# P10_ETH0_RGMII.net
KiCad netlist of a schematic drawn in Altium Designer
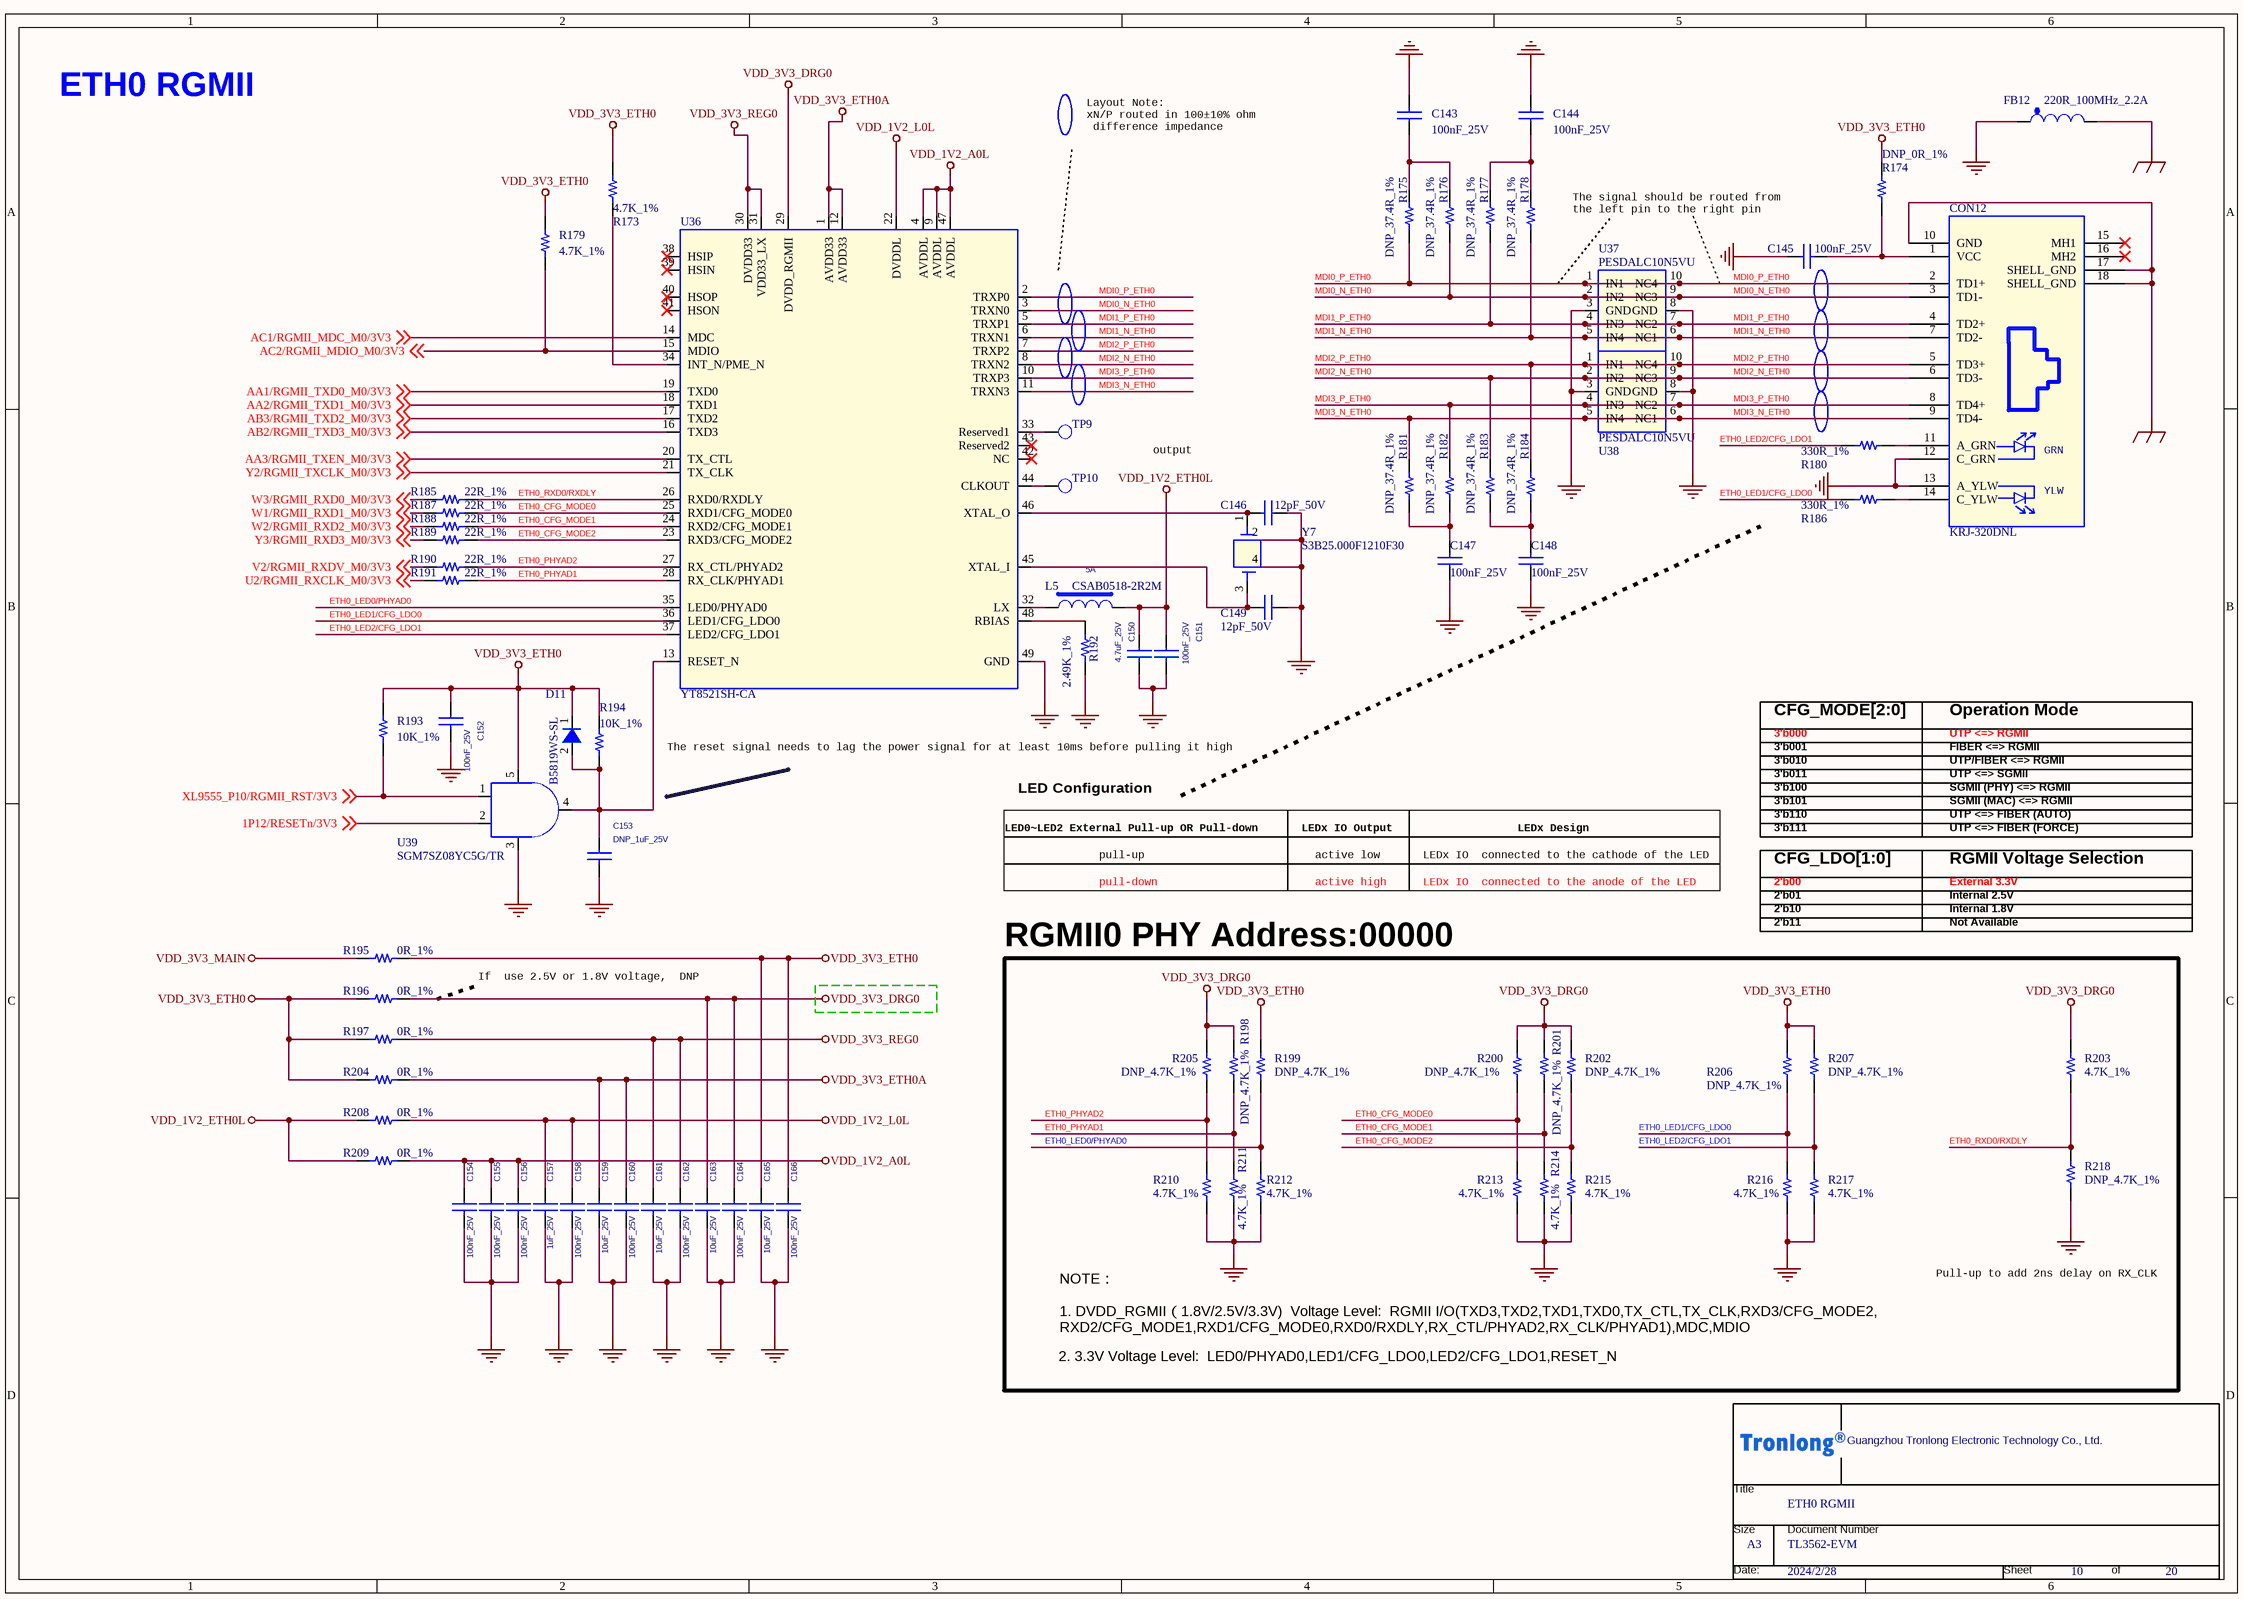
[diagram p0: P10_ETH0 RGMII.SchDoc]

(export (version "E")
  (design (tool "Eeschema 10.0.6"))
  (components
    (comp (ref "C143")
      (value "100nF_25V")
      (footprint "C0402")
      (description "贴片陶瓷电容,100nF,10%,25V,X5R")
      (libsource (lib "*") (part "CAP NP_Dup3"))
    )
    (comp (ref "C144")
      (value "100nF_25V")
      (footprint "C0402")
      (description "贴片陶瓷电容,100nF,10%,25V,X5R")
      (libsource (lib "*") (part "CAP NP_Dup3"))
    )
    (comp (ref "C145")
      (value "100nF_25V")
      (footprint "C0402")
      (description "贴片陶瓷电容,100nF,10%,25V,X5R")
      (libsource (lib "*") (part "CAP NP_Dup3"))
    )
    (comp (ref "C146")
      (value "12pF_50V")
      (footprint "C0402")
      (description "贴片陶瓷电容,12pF,5%,50V,COG")
      (libsource (lib "*") (part "CAP NP_Dup3"))
    )
    (comp (ref "C147")
      (value "100nF_25V")
      (footprint "C0402")
      (description "贴片陶瓷电容,100nF,10%,25V,X5R")
      (libsource (lib "*") (part "CAP NP_Dup3"))
    )
    (comp (ref "C148")
      (value "100nF_25V")
      (footprint "C0402")
      (description "贴片陶瓷电容,100nF,10%,25V,X5R")
      (libsource (lib "*") (part "CAP NP_Dup3"))
    )
    (comp (ref "C149")
      (value "12pF_50V")
      (footprint "C0402")
      (description "贴片陶瓷电容,12pF,5%,50V,COG")
      (libsource (lib "*") (part "CAP NP_Dup3"))
    )
    (comp (ref "C150")
      (value "4.7uF_25V")
      (footprint "C0603")
      (description "贴片陶瓷电容,4.7uF,10%,25V,X5R")
      (libsource (lib "*") (part "CAP NP_Dup3"))
    )
    (comp (ref "C151")
      (value "100nF_25V")
      (footprint "C0402")
      (description "贴片陶瓷电容,100nF,10%,25V,X5R")
      (libsource (lib "*") (part "CAP NP_Dup3"))
    )
    (comp (ref "C152")
      (value "100nF_25V")
      (footprint "C0402")
      (description "贴片陶瓷电容,100nF,10%,25V,X5R")
      (libsource (lib "*") (part "CAP NP_Dup3"))
    )
    (comp (ref "C153")
      (value "DNP_1uF_25V")
      (footprint "C0603")
      (description "贴片陶瓷电容,1uF,10%,25V,X5R")
      (libsource (lib "*") (part "CAP NP_Dup3"))
    )
    (comp (ref "C154")
      (value "100nF_25V")
      (footprint "C0402")
      (description "贴片陶瓷电容,100nF,10%,25V,X5R")
      (libsource (lib "*") (part "CAP NP_Dup3"))
    )
    (comp (ref "C155")
      (value "100nF_25V")
      (footprint "C0402")
      (description "贴片陶瓷电容,100nF,10%,25V,X5R")
      (libsource (lib "*") (part "CAP NP_Dup3"))
    )
    (comp (ref "C156")
      (value "100nF_25V")
      (footprint "C0402")
      (description "贴片陶瓷电容,100nF,10%,25V,X5R")
      (libsource (lib "*") (part "CAP NP_Dup3"))
    )
    (comp (ref "C157")
      (value "1uF_25V")
      (footprint "C0603")
      (description "贴片陶瓷电容,1uF,10%,25V,X5R")
      (libsource (lib "*") (part "CAP NP_Dup3"))
    )
    (comp (ref "C158")
      (value "100nF_25V")
      (footprint "C0402")
      (description "贴片陶瓷电容,100nF,10%,25V,X5R")
      (libsource (lib "*") (part "CAP NP_Dup3"))
    )
    (comp (ref "C159")
      (value "10uF_25V")
      (footprint "C0603")
      (description "贴片陶瓷电容,10uF,10%,10V,X5R")
      (libsource (lib "*") (part "CAP NP_Dup3"))
    )
    (comp (ref "C160")
      (value "100nF_25V")
      (footprint "C0402")
      (description "贴片陶瓷电容,100nF,10%,25V,X5R")
      (libsource (lib "*") (part "CAP NP_Dup3"))
    )
    (comp (ref "C161")
      (value "10uF_25V")
      (footprint "C0603")
      (description "贴片陶瓷电容,10uF,10%,10V,X5R")
      (libsource (lib "*") (part "CAP NP_Dup3"))
    )
    (comp (ref "C162")
      (value "100nF_25V")
      (footprint "C0402")
      (description "贴片陶瓷电容,100nF,10%,25V,X5R")
      (libsource (lib "*") (part "CAP NP_Dup3"))
    )
    (comp (ref "C163")
      (value "10uF_25V")
      (footprint "C0603")
      (description "贴片陶瓷电容,10uF,10%,10V,X5R")
      (libsource (lib "*") (part "CAP NP_Dup3"))
    )
    (comp (ref "C164")
      (value "100nF_25V")
      (footprint "C0402")
      (description "贴片陶瓷电容,100nF,10%,25V,X5R")
      (libsource (lib "*") (part "CAP NP_Dup3"))
    )
    (comp (ref "C165")
      (value "10uF_25V")
      (footprint "C0603")
      (description "贴片陶瓷电容,10uF,10%,10V,X5R")
      (libsource (lib "*") (part "CAP NP_Dup3"))
    )
    (comp (ref "C166")
      (value "100nF_25V")
      (footprint "C0402")
      (description "贴片陶瓷电容,100nF,10%,25V,X5R")
      (libsource (lib "*") (part "CAP NP_Dup3"))
    )
    (comp (ref "CON12")
      (value "KRJ-320DNL")
      (footprint "KRJ-320DNL_14P")
      (description "RJ45连接器,14PIN,90度,母座,插件")
      (fields (field (name "MANUFACTURER") "东莞市科优达电子科技有限公司（DGKYD）"))
      (libsource (lib "*") (part "KRJ-320DNL_1"))
    )
    (comp (ref "D11")
      (value "B5819WS-SL")
      (footprint "SOD-323")
      (description "肖特基二极管,VR=40V,IF=1A,VF=0.6V@1A")
      (fields (field (name "MFR") "On Semiconductor") (field (name "TIINTPARTNUMBER") "1E0013"))
      (libsource (lib "TL3562-EVM-A1-0-000-D-20231116") (part "Diode200mA250V"))
    )
    (comp (ref "FB12")
      (value "220R_100MHz_2.2A")
      (footprint "L0603")
      (description "磁珠,50mΩ,2.2A,220R@100MHz")
      (fields
        (field (name "MANUFACTURER") "深圳顺络电子股份有限公司（Sunlord）")
        (field (name "MANUFACTURER PARTNUMBER") "UPZ1608U221-2R2TF")
      )
      (libsource (lib "*") (part "FERRITE BEAD_Dup2"))
    )
    (comp (ref "L5")
      (value "CSAB0518-2R2M")
      (footprint "SMD-L2520M-2P")
      (description "贴片功率电感,2.2uH,0.035Ω,Isat=6.5A,Irms=5A")
      (fields (field (name "CURRENT") "5A") (field (name "MANUFACTURER") "深圳市科达嘉电子有限公司（CODACA）"))
      (libsource (lib "TL3562-EVM-A1-0-000-D-20231116") (part "INDUCTOR"))
    )
    (comp (ref "R173")
      (value "4.7K_1%")
      (footprint "R0402")
      (description "贴片电阻,4.7K,±1%,1/16W")
      (libsource (lib "*") (part "Resistor_Dup3"))
    )
    (comp (ref "R174")
      (value "DNP_0R_1%")
      (footprint "R0402")
      (description "贴片电阻,0R,±1%,1/16W")
      (libsource (lib "*") (part "Resistor_Dup3"))
    )
    (comp (ref "R175")
      (value "DNP_37.4R_1%")
      (footprint "R0603")
      (description "37.4R,±1%,R0603,≥1/10W")
      (libsource (lib "*") (part "Resistor_Dup3"))
    )
    (comp (ref "R176")
      (value "DNP_37.4R_1%")
      (footprint "R0603")
      (description "37.4R,±1%,R0603,≥1/10W")
      (libsource (lib "*") (part "Resistor_Dup3"))
    )
    (comp (ref "R177")
      (value "DNP_37.4R_1%")
      (footprint "R0603")
      (description "37.4R,±1%,R0603,≥1/10W")
      (libsource (lib "*") (part "Resistor_Dup3"))
    )
    (comp (ref "R178")
      (value "DNP_37.4R_1%")
      (footprint "R0603")
      (description "37.4R,±1%,R0603,≥1/10W")
      (libsource (lib "*") (part "Resistor_Dup3"))
    )
    (comp (ref "R179")
      (value "4.7K_1%")
      (footprint "R0402")
      (description "贴片电阻,4.7K,±1%,1/16W")
      (libsource (lib "*") (part "Resistor_Dup3"))
    )
    (comp (ref "R180")
      (value "330R_1%")
      (footprint "R0402")
      (description "贴片电阻,330R,±1%,1/16W")
      (libsource (lib "*") (part "Resistor_Dup3"))
    )
    (comp (ref "R181")
      (value "DNP_37.4R_1%")
      (footprint "R0603")
      (description "37.4R,±1%,R0603,≥1/10W")
      (libsource (lib "*") (part "Resistor_Dup3"))
    )
    (comp (ref "R182")
      (value "DNP_37.4R_1%")
      (footprint "R0603")
      (description "37.4R,±1%,R0603,≥1/10W")
      (libsource (lib "*") (part "Resistor_Dup3"))
    )
    (comp (ref "R183")
      (value "DNP_37.4R_1%")
      (footprint "R0603")
      (description "37.4R,±1%,R0603,≥1/10W")
      (libsource (lib "*") (part "Resistor_Dup3"))
    )
    (comp (ref "R184")
      (value "DNP_37.4R_1%")
      (footprint "R0603")
      (description "37.4R,±1%,R0603,≥1/10W")
      (libsource (lib "*") (part "Resistor_Dup3"))
    )
    (comp (ref "R185")
      (value "22R_1%")
      (footprint "R0402")
      (description "贴片电阻,22R,±1%,1/16W")
      (libsource (lib "*") (part "Resistor_Dup3"))
    )
    (comp (ref "R186")
      (value "330R_1%")
      (footprint "R0402")
      (description "贴片电阻,330R,±1%,1/16W")
      (libsource (lib "*") (part "Resistor_Dup3"))
    )
    (comp (ref "R187")
      (value "22R_1%")
      (footprint "R0402")
      (description "贴片电阻,22R,±1%,1/16W")
      (libsource (lib "*") (part "Resistor_Dup3"))
    )
    (comp (ref "R188")
      (value "22R_1%")
      (footprint "R0402")
      (description "贴片电阻,22R,±1%,1/16W")
      (libsource (lib "*") (part "Resistor_Dup3"))
    )
    (comp (ref "R189")
      (value "22R_1%")
      (footprint "R0402")
      (description "贴片电阻,22R,±1%,1/16W")
      (libsource (lib "*") (part "Resistor_Dup3"))
    )
    (comp (ref "R190")
      (value "22R_1%")
      (footprint "R0402")
      (description "贴片电阻,22R,±1%,1/16W")
      (libsource (lib "*") (part "Resistor_Dup3"))
    )
    (comp (ref "R191")
      (value "22R_1%")
      (footprint "R0402")
      (description "贴片电阻,22R,±1%,1/16W")
      (libsource (lib "*") (part "Resistor_Dup3"))
    )
    (comp (ref "R192")
      (value "2.49K_1%")
      (footprint "R0603")
      (description "贴片电阻,2.49K,±1%,1/10W")
      (libsource (lib "*") (part "Resistor_Dup3"))
    )
    (comp (ref "R193")
      (value "10K_1%")
      (footprint "R0402")
      (description "贴片电阻,10K,±1%,1/16W")
      (libsource (lib "*") (part "Resistor_Dup3"))
    )
    (comp (ref "R194")
      (value "10K_1%")
      (footprint "R0402")
      (description "贴片电阻,10K,±1%,1/16W")
      (libsource (lib "*") (part "Resistor_Dup3"))
    )
    (comp (ref "R195")
      (value "0R_1%")
      (footprint "R0603")
      (description "0R,±1%,R0603,≥1/10W")
      (libsource (lib "*") (part "Resistor_Dup3"))
    )
    (comp (ref "R196")
      (value "0R_1%")
      (footprint "R0603")
      (description "0R,±1%,R0603,≥1/10W")
      (libsource (lib "*") (part "Resistor_Dup3"))
    )
    (comp (ref "R197")
      (value "0R_1%")
      (footprint "R0603")
      (description "0R,±1%,R0603,≥1/10W")
      (libsource (lib "*") (part "Resistor_Dup3"))
    )
    (comp (ref "R198")
      (value "DNP_4.7K_1%")
      (footprint "R0402")
      (description "贴片电阻,4.7K,±1%,1/16W")
      (libsource (lib "*") (part "Resistor_Dup3"))
    )
    (comp (ref "R199")
      (value "DNP_4.7K_1%")
      (footprint "R0402")
      (description "贴片电阻,4.7K,±1%,1/16W")
      (libsource (lib "*") (part "Resistor_Dup3"))
    )
    (comp (ref "R200")
      (value "DNP_4.7K_1%")
      (footprint "R0402")
      (description "贴片电阻,4.7K,±1%,1/16W")
      (libsource (lib "*") (part "Resistor_Dup3"))
    )
    (comp (ref "R201")
      (value "DNP_4.7K_1%")
      (footprint "R0402")
      (description "贴片电阻,4.7K,±1%,1/16W")
      (libsource (lib "*") (part "Resistor_Dup3"))
    )
    (comp (ref "R202")
      (value "DNP_4.7K_1%")
      (footprint "R0402")
      (description "贴片电阻,4.7K,±1%,1/16W")
      (libsource (lib "*") (part "Resistor_Dup3"))
    )
    (comp (ref "R203")
      (value "4.7K_1%")
      (footprint "R0402")
      (description "贴片电阻,4.7K,±1%,1/16W")
      (libsource (lib "*") (part "Resistor_Dup3"))
    )
    (comp (ref "R204")
      (value "0R_1%")
      (footprint "R0603")
      (description "0R,±1%,R0603,≥1/10W")
      (libsource (lib "*") (part "Resistor_Dup3"))
    )
    (comp (ref "R205")
      (value "DNP_4.7K_1%")
      (footprint "R0402")
      (description "贴片电阻,4.7K,±1%,1/16W")
      (libsource (lib "*") (part "Resistor_Dup3"))
    )
    (comp (ref "R206")
      (value "DNP_4.7K_1%")
      (footprint "R0402")
      (description "贴片电阻,4.7K,±1%,1/16W")
      (libsource (lib "*") (part "Resistor_Dup3"))
    )
    (comp (ref "R207")
      (value "DNP_4.7K_1%")
      (footprint "R0402")
      (description "贴片电阻,4.7K,±1%,1/16W")
      (libsource (lib "*") (part "Resistor_Dup3"))
    )
    (comp (ref "R208")
      (value "0R_1%")
      (footprint "R0603")
      (description "0R,±1%,R0603,≥1/10W")
      (libsource (lib "*") (part "Resistor_Dup3"))
    )
    (comp (ref "R209")
      (value "0R_1%")
      (footprint "R0603")
      (description "0R,±1%,R0603,≥1/10W")
      (libsource (lib "*") (part "Resistor_Dup3"))
    )
    (comp (ref "R210")
      (value "4.7K_1%")
      (footprint "R0402")
      (description "贴片电阻,4.7K,±1%,1/16W")
      (libsource (lib "*") (part "Resistor_Dup3"))
    )
    (comp (ref "R211")
      (value "4.7K_1%")
      (footprint "R0402")
      (description "贴片电阻,4.7K,±1%,1/16W")
      (libsource (lib "*") (part "Resistor_Dup3"))
    )
    (comp (ref "R212")
      (value "4.7K_1%")
      (footprint "R0402")
      (description "贴片电阻,4.7K,±1%,1/16W")
      (libsource (lib "*") (part "Resistor_Dup3"))
    )
    (comp (ref "R213")
      (value "4.7K_1%")
      (footprint "R0402")
      (description "贴片电阻,4.7K,±1%,1/16W")
      (libsource (lib "*") (part "Resistor_Dup3"))
    )
    (comp (ref "R214")
      (value "4.7K_1%")
      (footprint "R0402")
      (description "贴片电阻,4.7K,±1%,1/16W")
      (libsource (lib "*") (part "Resistor_Dup3"))
    )
    (comp (ref "R215")
      (value "4.7K_1%")
      (footprint "R0402")
      (description "贴片电阻,4.7K,±1%,1/16W")
      (libsource (lib "*") (part "Resistor_Dup3"))
    )
    (comp (ref "R216")
      (value "4.7K_1%")
      (footprint "R0402")
      (description "贴片电阻,4.7K,±1%,1/16W")
      (libsource (lib "*") (part "Resistor_Dup3"))
    )
    (comp (ref "R217")
      (value "4.7K_1%")
      (footprint "R0402")
      (description "贴片电阻,4.7K,±1%,1/16W")
      (libsource (lib "*") (part "Resistor_Dup3"))
    )
    (comp (ref "R218")
      (value "DNP_4.7K_1%")
      (footprint "R0402")
      (description "贴片电阻,4.7K,±1%,1/16W")
      (libsource (lib "*") (part "Resistor_Dup3"))
    )
    (comp (ref "TP9") (value "SMT TP") (footprint "TP30") (libsource (lib "*") (part "T POINT R")))
    (comp (ref "TP10") (value "SMT TP") (footprint "TP30") (libsource (lib "*") (part "T POINT R")))
    (comp (ref "U36")
      (value "YT8521SH-CA")
      (footprint "QFN48")
      (description "以太网收发器，RGMII/SGMII")
      (fields (field (name "MANUFACTURER") "苏州裕太微电子有限公司（Motorcomm）"))
      (libsource (lib "*") (part "YT8521S"))
    )
    (comp (ref "U37")
      (value "PESDALC10N5VU")
      (footprint "DFN-10-2510")
      (description "4通道超低电容瞬态抑制器")
      (fields (field (name "MANUFACTURER") "上海芯导电子科技有限公司（Prisemi）"))
      (libsource (lib "*") (part "SU099PGTR"))
    )
    (comp (ref "U38")
      (value "PESDALC10N5VU")
      (footprint "DFN-10-2510")
      (description "4通道超低电容瞬态抑制器")
      (fields (field (name "MANUFACTURER") "上海芯导电子科技有限公司（Prisemi）"))
      (libsource (lib "*") (part "SU099PGTR"))
    )
    (comp (ref "U39")
      (value "SGM7SZ08YC5G/TR")
      (footprint "SC70-5-43M")
      (description "1个两输入与门")
      (fields (field (name "MANUFACTURER") "圣邦微电子股份有限公司（SGMICRO）"))
      (libsource (lib "*") (part "74LVC1G08"))
    )
    (comp (ref "Y7")
      (value "S3B25.000F1210F30")
      (footprint "SMD_3225")
      (description "四脚无源晶振,25MHz,±10ppm,12pF,30Ω,±30ppm")
      (fields (field (name "MANUFACTURER") "深圳市星通时频电子有限公司公司（JSCJ）"))
      (libsource (lib "*") (part "CRYSTAL-4 PIN"))
    )
  )
  (nets
    (net (code "1") (name "/ETH0_CFG_MODE0") (class "Default")
      (node (ref "R187") (pin "2") (pinfunction "2_2") (pintype "passive"))
      (node (ref "R200") (pin "1") (pinfunction "1_1") (pintype "passive"))
      (node (ref "R213") (pin "2") (pinfunction "2_2") (pintype "passive"))
      (node (ref "U36") (pin "25") (pinfunction "RXD1/CFG_MODE0_25") (pintype "passive"))
    )
    (net (code "2") (name "/ETH0_CFG_MODE1") (class "Default")
      (node (ref "R188") (pin "2") (pinfunction "2_2") (pintype "passive"))
      (node (ref "R201") (pin "1") (pinfunction "1_1") (pintype "passive"))
      (node (ref "R214") (pin "2") (pinfunction "2_2") (pintype "passive"))
      (node (ref "U36") (pin "24") (pinfunction "RXD2/CFG_MODE1_24") (pintype "passive"))
    )
    (net (code "3") (name "/ETH0_CFG_MODE2") (class "Default")
      (node (ref "R189") (pin "2") (pinfunction "2_2") (pintype "passive"))
      (node (ref "R202") (pin "1") (pinfunction "1_1") (pintype "passive"))
      (node (ref "R215") (pin "2") (pinfunction "2_2") (pintype "passive"))
      (node (ref "U36") (pin "23") (pinfunction "RXD3/CFG_MODE2_23") (pintype "passive"))
    )
    (net (code "4") (name "/ETH0_LED0{slash}PHYAD0") (class "Default")
      (node (ref "R199") (pin "1") (pinfunction "1_1") (pintype "passive"))
      (node (ref "R212") (pin "2") (pinfunction "2_2") (pintype "passive"))
      (node (ref "U36") (pin "35") (pinfunction "LED0/PHYAD0_35") (pintype "passive"))
    )
    (net (code "5") (name "/ETH0_LED1{slash}CFG_LDO0") (class "Default")
      (node (ref "R186") (pin "1") (pinfunction "1_1") (pintype "passive"))
      (node (ref "R206") (pin "1") (pinfunction "1_1") (pintype "passive"))
      (node (ref "R216") (pin "2") (pinfunction "2_2") (pintype "passive"))
      (node (ref "U36") (pin "36") (pinfunction "LED1/CFG_LDO0_36") (pintype "passive"))
    )
    (net (code "6") (name "/ETH0_LED2{slash}CFG_LDO1") (class "Default")
      (node (ref "R180") (pin "1") (pinfunction "1_1") (pintype "passive"))
      (node (ref "R207") (pin "1") (pinfunction "1_1") (pintype "passive"))
      (node (ref "R217") (pin "2") (pinfunction "2_2") (pintype "passive"))
      (node (ref "U36") (pin "37") (pinfunction "LED2/CFG_LDO1_37") (pintype "passive"))
    )
    (net (code "7") (name "/ETH0_PHYAD1") (class "Default")
      (node (ref "R191") (pin "2") (pinfunction "2_2") (pintype "passive"))
      (node (ref "R198") (pin "1") (pinfunction "1_1") (pintype "passive"))
      (node (ref "R211") (pin "2") (pinfunction "2_2") (pintype "passive"))
      (node (ref "U36") (pin "28") (pinfunction "RX_CLK/PHYAD1_28") (pintype "passive"))
    )
    (net (code "8") (name "/ETH0_PHYAD2") (class "Default")
      (node (ref "R190") (pin "2") (pinfunction "2_2") (pintype "passive"))
      (node (ref "R205") (pin "1") (pinfunction "1_1") (pintype "passive"))
      (node (ref "R210") (pin "2") (pinfunction "2_2") (pintype "passive"))
      (node (ref "U36") (pin "27") (pinfunction "RX_CTL/PHYAD2_27") (pintype "passive"))
    )
    (net (code "9") (name "/ETH0_RXD0{slash}RXDLY") (class "Default")
      (node (ref "R185") (pin "2") (pinfunction "2_2") (pintype "passive"))
      (node (ref "R203") (pin "1") (pinfunction "1_1") (pintype "passive"))
      (node (ref "R218") (pin "2") (pinfunction "2_2") (pintype "passive"))
      (node (ref "U36") (pin "26") (pinfunction "RXD0/RXDLY_26") (pintype "passive"))
    )
    (net (code "10") (name "/MDI0_N_ETH0") (class "Default")
      (node (ref "CON12") (pin "3") (pinfunction "TD1-_3") (pintype "passive"))
      (node (ref "R176") (pin "2") (pinfunction "2_2") (pintype "passive"))
      (node (ref "U36") (pin "3") (pinfunction "TRXN0_3") (pintype "passive"))
      (node (ref "U37") (pin "2") (pinfunction "IN2_2") (pintype "passive"))
      (node (ref "U37") (pin "9") (pinfunction "NC3_9") (pintype "passive"))
    )
    (net (code "11") (name "/MDI0_P_ETH0") (class "Default")
      (node (ref "CON12") (pin "2") (pinfunction "TD1+_2") (pintype "passive"))
      (node (ref "R175") (pin "2") (pinfunction "2_2") (pintype "passive"))
      (node (ref "U36") (pin "2") (pinfunction "TRXP0_2") (pintype "passive"))
      (node (ref "U37") (pin "1") (pinfunction "IN1_1") (pintype "passive"))
      (node (ref "U37") (pin "10") (pinfunction "NC4_10") (pintype "passive"))
    )
    (net (code "12") (name "/MDI1_N_ETH0") (class "Default")
      (node (ref "CON12") (pin "7") (pinfunction "TD2-_7") (pintype "passive"))
      (node (ref "R178") (pin "2") (pinfunction "2_2") (pintype "passive"))
      (node (ref "U36") (pin "6") (pinfunction "TRXN1_6") (pintype "passive"))
      (node (ref "U37") (pin "5") (pinfunction "IN4_5") (pintype "passive"))
      (node (ref "U37") (pin "6") (pinfunction "NC1_6") (pintype "passive"))
    )
    (net (code "13") (name "/MDI1_P_ETH0") (class "Default")
      (node (ref "CON12") (pin "4") (pinfunction "TD2+_4") (pintype "passive"))
      (node (ref "R177") (pin "2") (pinfunction "2_2") (pintype "passive"))
      (node (ref "U36") (pin "5") (pinfunction "TRXP1_5") (pintype "passive"))
      (node (ref "U37") (pin "4") (pinfunction "IN3_4") (pintype "passive"))
      (node (ref "U37") (pin "7") (pinfunction "NC2_7") (pintype "passive"))
    )
    (net (code "14") (name "/MDI2_N_ETH0") (class "Default")
      (node (ref "CON12") (pin "6") (pinfunction "TD3-_6") (pintype "passive"))
      (node (ref "R183") (pin "1") (pinfunction "1_1") (pintype "passive"))
      (node (ref "U36") (pin "8") (pinfunction "TRXN2_8") (pintype "passive"))
      (node (ref "U38") (pin "2") (pinfunction "IN2_2") (pintype "passive"))
      (node (ref "U38") (pin "9") (pinfunction "NC3_9") (pintype "passive"))
    )
    (net (code "15") (name "/MDI2_P_ETH0") (class "Default")
      (node (ref "CON12") (pin "5") (pinfunction "TD3+_5") (pintype "passive"))
      (node (ref "R184") (pin "1") (pinfunction "1_1") (pintype "passive"))
      (node (ref "U36") (pin "7") (pinfunction "TRXP2_7") (pintype "passive"))
      (node (ref "U38") (pin "1") (pinfunction "IN1_1") (pintype "passive"))
      (node (ref "U38") (pin "10") (pinfunction "NC4_10") (pintype "passive"))
    )
    (net (code "16") (name "/MDI3_N_ETH0") (class "Default")
      (node (ref "CON12") (pin "9") (pinfunction "TD4-_9") (pintype "passive"))
      (node (ref "R181") (pin "1") (pinfunction "1_1") (pintype "passive"))
      (node (ref "U36") (pin "11") (pinfunction "TRXN3_11") (pintype "passive"))
      (node (ref "U38") (pin "5") (pinfunction "IN4_5") (pintype "passive"))
      (node (ref "U38") (pin "6") (pinfunction "NC1_6") (pintype "passive"))
    )
    (net (code "17") (name "/MDI3_P_ETH0") (class "Default")
      (node (ref "CON12") (pin "8") (pinfunction "TD4+_8") (pintype "passive"))
      (node (ref "R182") (pin "1") (pinfunction "1_1") (pintype "passive"))
      (node (ref "U36") (pin "10") (pinfunction "TRXP3_10") (pintype "passive"))
      (node (ref "U38") (pin "4") (pinfunction "IN3_4") (pintype "passive"))
      (node (ref "U38") (pin "7") (pinfunction "NC2_7") (pintype "passive"))
    )
    (net (code "18") (name "1P12{slash}RESETn{slash}3V3") (class "Default")
      (node (ref "U39") (pin "2") (pinfunction "B_2") (pintype "passive"))
    )
    (net (code "19") (name "AA1{slash}RGMII_TXD0_M0{slash}3V3") (class "Default")
      (node (ref "U36") (pin "19") (pinfunction "TXD0_19") (pintype "passive"))
    )
    (net (code "20") (name "AA2{slash}RGMII_TXD1_M0{slash}3V3") (class "Default")
      (node (ref "U36") (pin "18") (pinfunction "TXD1_18") (pintype "passive"))
    )
    (net (code "21") (name "AA3{slash}RGMII_TXEN_M0{slash}3V3") (class "Default")
      (node (ref "U36") (pin "20") (pinfunction "TX_CTL_20") (pintype "passive"))
    )
    (net (code "22") (name "AB2{slash}RGMII_TXD3_M0{slash}3V3") (class "Default")
      (node (ref "U36") (pin "16") (pinfunction "TXD3_16") (pintype "passive"))
    )
    (net (code "23") (name "AB3{slash}RGMII_TXD2_M0{slash}3V3") (class "Default")
      (node (ref "U36") (pin "17") (pinfunction "TXD2_17") (pintype "passive"))
    )
    (net (code "24") (name "AC1{slash}RGMII_MDC_M0{slash}3V3") (class "Default")
      (node (ref "U36") (pin "14") (pinfunction "MDC_14") (pintype "passive"))
    )
    (net (code "25") (name "AC2{slash}RGMII_MDIO_M0{slash}3V3") (class "Default")
      (node (ref "R179") (pin "2") (pinfunction "2_2") (pintype "passive"))
      (node (ref "U36") (pin "15") (pinfunction "MDIO_15") (pintype "passive"))
    )
    (net (code "26") (name "EGND") (class "Default")
      (node (ref "CON12") (pin "10") (pinfunction "GND_10") (pintype "passive"))
      (node (ref "CON12") (pin "17") (pinfunction "SHELL_GND_17") (pintype "power_in"))
      (node (ref "CON12") (pin "18") (pinfunction "SHELL_GND_18") (pintype "power_in"))
      (node (ref "FB12") (pin "2") (pinfunction "2_2") (pintype "passive"))
    )
    (net (code "27") (name "GND") (class "Default")
      (node (ref "C143") (pin "2") (pinfunction "2_2") (pintype "passive"))
      (node (ref "C144") (pin "2") (pinfunction "2_2") (pintype "passive"))
      (node (ref "C145") (pin "1") (pinfunction "1_1") (pintype "passive"))
      (node (ref "C146") (pin "1") (pinfunction "1_1") (pintype "passive"))
      (node (ref "C147") (pin "1") (pinfunction "1_1") (pintype "passive"))
      (node (ref "C148") (pin "1") (pinfunction "1_1") (pintype "passive"))
      (node (ref "C149") (pin "1") (pinfunction "1_1") (pintype "passive"))
      (node (ref "C150") (pin "2") (pinfunction "2_2") (pintype "passive"))
      (node (ref "C151") (pin "2") (pinfunction "2_2") (pintype "passive"))
      (node (ref "C152") (pin "2") (pinfunction "2_2") (pintype "passive"))
      (node (ref "C153") (pin "2") (pinfunction "2_2") (pintype "passive"))
      (node (ref "C154") (pin "2") (pinfunction "2_2") (pintype "passive"))
      (node (ref "C155") (pin "2") (pinfunction "2_2") (pintype "passive"))
      (node (ref "C156") (pin "2") (pinfunction "2_2") (pintype "passive"))
      (node (ref "C157") (pin "2") (pinfunction "2_2") (pintype "passive"))
      (node (ref "C158") (pin "2") (pinfunction "2_2") (pintype "passive"))
      (node (ref "C159") (pin "2") (pinfunction "2_2") (pintype "passive"))
      (node (ref "C160") (pin "2") (pinfunction "2_2") (pintype "passive"))
      (node (ref "C161") (pin "2") (pinfunction "2_2") (pintype "passive"))
      (node (ref "C162") (pin "2") (pinfunction "2_2") (pintype "passive"))
      (node (ref "C163") (pin "2") (pinfunction "2_2") (pintype "passive"))
      (node (ref "C164") (pin "2") (pinfunction "2_2") (pintype "passive"))
      (node (ref "C165") (pin "2") (pinfunction "2_2") (pintype "passive"))
      (node (ref "C166") (pin "2") (pinfunction "2_2") (pintype "passive"))
      (node (ref "CON12") (pin "12") (pinfunction "C_GRN_12") (pintype "passive"))
      (node (ref "CON12") (pin "13") (pinfunction "A_YLW_13") (pintype "passive"))
      (node (ref "FB12") (pin "1") (pinfunction "1_1") (pintype "passive"))
      (node (ref "R192") (pin "1") (pinfunction "1_1") (pintype "passive"))
      (node (ref "R210") (pin "1") (pinfunction "1_1") (pintype "passive"))
      (node (ref "R211") (pin "1") (pinfunction "1_1") (pintype "passive"))
      (node (ref "R212") (pin "1") (pinfunction "1_1") (pintype "passive"))
      (node (ref "R213") (pin "1") (pinfunction "1_1") (pintype "passive"))
      (node (ref "R214") (pin "1") (pinfunction "1_1") (pintype "passive"))
      (node (ref "R215") (pin "1") (pinfunction "1_1") (pintype "passive"))
      (node (ref "R216") (pin "1") (pinfunction "1_1") (pintype "passive"))
      (node (ref "R217") (pin "1") (pinfunction "1_1") (pintype "passive"))
      (node (ref "R218") (pin "1") (pinfunction "1_1") (pintype "passive"))
      (node (ref "U36") (pin "49") (pinfunction "GND_49") (pintype "power_in"))
      (node (ref "U37") (pin "3") (pinfunction "GND_3") (pintype "power_in"))
      (node (ref "U37") (pin "8") (pinfunction "GND_8") (pintype "power_in"))
      (node (ref "U38") (pin "3") (pinfunction "GND_3") (pintype "power_in"))
      (node (ref "U38") (pin "8") (pinfunction "GND_8") (pintype "power_in"))
      (node (ref "U39") (pin "3") (pinfunction "GND_3") (pintype "passive"))
      (node (ref "Y7") (pin "2") (pinfunction "2_2") (pintype "passive"))
      (node (ref "Y7") (pin "4") (pinfunction "4_4") (pintype "passive"))
    )
    (net (code "28") (name "Net-(C143-Pad1)") (class "Default")
      (node (ref "C143") (pin "1") (pinfunction "1_1") (pintype "passive"))
      (node (ref "R175") (pin "1") (pinfunction "1_1") (pintype "passive"))
      (node (ref "R176") (pin "1") (pinfunction "1_1") (pintype "passive"))
    )
    (net (code "29") (name "Net-(C144-Pad1)") (class "Default")
      (node (ref "C144") (pin "1") (pinfunction "1_1") (pintype "passive"))
      (node (ref "R177") (pin "1") (pinfunction "1_1") (pintype "passive"))
      (node (ref "R178") (pin "1") (pinfunction "1_1") (pintype "passive"))
    )
    (net (code "30") (name "Net-(C147-Pad2)") (class "Default")
      (node (ref "C147") (pin "2") (pinfunction "2_2") (pintype "passive"))
      (node (ref "R181") (pin "2") (pinfunction "2_2") (pintype "passive"))
      (node (ref "R182") (pin "2") (pinfunction "2_2") (pintype "passive"))
    )
    (net (code "31") (name "Net-(C148-Pad2)") (class "Default")
      (node (ref "C148") (pin "2") (pinfunction "2_2") (pintype "passive"))
      (node (ref "R183") (pin "2") (pinfunction "2_2") (pintype "passive"))
      (node (ref "R184") (pin "2") (pinfunction "2_2") (pintype "passive"))
    )
    (net (code "32") (name "Net-(CON12-A_GRN)") (class "Default")
      (node (ref "CON12") (pin "11") (pinfunction "A_GRN_11") (pintype "passive"))
      (node (ref "R180") (pin "2") (pinfunction "2_2") (pintype "passive"))
    )
    (net (code "33") (name "Net-(CON12-C_YLW)") (class "Default")
      (node (ref "CON12") (pin "14") (pinfunction "C_YLW_14") (pintype "passive"))
      (node (ref "R186") (pin "2") (pinfunction "2_2") (pintype "passive"))
    )
    (net (code "34") (name "Net-(CON12-VCC)") (class "Default")
      (node (ref "C145") (pin "2") (pinfunction "2_2") (pintype "passive"))
      (node (ref "CON12") (pin "1") (pinfunction "VCC_1") (pintype "passive"))
      (node (ref "R174") (pin "2") (pinfunction "2_2") (pintype "passive"))
    )
    (net (code "35") (name "Net-(D11-Anode)") (class "Default")
      (node (ref "C153") (pin "1") (pinfunction "1_1") (pintype "passive"))
      (node (ref "D11") (pin "2") (pinfunction "Anode_2") (pintype "passive"))
      (node (ref "R194") (pin "1") (pinfunction "1_1") (pintype "passive"))
      (node (ref "U36") (pin "13") (pinfunction "RESET_N_13") (pintype "passive"))
      (node (ref "U39") (pin "4") (pinfunction "Y_4") (pintype "passive"))
    )
    (net (code "36") (name "Net-(TP9-TP)") (class "Default")
      (node (ref "TP9") (pin "1") (pinfunction "TP_1") (pintype "passive"))
      (node (ref "U36") (pin "33") (pinfunction "Reserved1_33") (pintype "passive"))
    )
    (net (code "37") (name "Net-(TP10-TP)") (class "Default")
      (node (ref "TP10") (pin "1") (pinfunction "TP_1") (pintype "passive"))
      (node (ref "U36") (pin "44") (pinfunction "CLKOUT_44") (pintype "passive"))
    )
    (net (code "38") (name "Net-(U36-INT_N{slash}PME_N)") (class "Default")
      (node (ref "R173") (pin "1") (pinfunction "1_1") (pintype "passive"))
      (node (ref "U36") (pin "34") (pinfunction "INT_N/PME_N_34") (pintype "passive"))
    )
    (net (code "39") (name "Net-(U36-LX)") (class "Default")
      (node (ref "L5") (pin "1") (pinfunction "1_1") (pintype "passive"))
      (node (ref "U36") (pin "32") (pinfunction "LX_32") (pintype "power_in"))
    )
    (net (code "40") (name "Net-(U36-RBIAS)") (class "Default")
      (node (ref "R192") (pin "2") (pinfunction "2_2") (pintype "passive"))
      (node (ref "U36") (pin "48") (pinfunction "RBIAS_48") (pintype "passive"))
    )
    (net (code "41") (name "Net-(U36-XTAL_I)") (class "Default")
      (node (ref "C149") (pin "2") (pinfunction "2_2") (pintype "passive"))
      (node (ref "U36") (pin "45") (pinfunction "XTAL_I_45") (pintype "passive"))
      (node (ref "Y7") (pin "3") (pinfunction "3_3") (pintype "passive"))
    )
    (net (code "42") (name "Net-(U36-XTAL_O)") (class "Default")
      (node (ref "C146") (pin "2") (pinfunction "2_2") (pintype "passive"))
      (node (ref "U36") (pin "46") (pinfunction "XTAL_O_46") (pintype "passive"))
      (node (ref "Y7") (pin "1") (pinfunction "1_1") (pintype "passive"))
    )
    (net (code "43") (name "U2{slash}RGMII_RXCLK_M0{slash}3V3") (class "Default")
      (node (ref "R191") (pin "1") (pinfunction "1_1") (pintype "passive"))
    )
    (net (code "44") (name "V2{slash}RGMII_RXDV_M0{slash}3V3") (class "Default")
      (node (ref "R190") (pin "1") (pinfunction "1_1") (pintype "passive"))
    )
    (net (code "45") (name "VDD_1V2_A0L") (class "Default")
      (node (ref "C154") (pin "1") (pinfunction "1_1") (pintype "passive"))
      (node (ref "C155") (pin "1") (pinfunction "1_1") (pintype "passive"))
      (node (ref "C156") (pin "1") (pinfunction "1_1") (pintype "passive"))
      (node (ref "R209") (pin "2") (pinfunction "2_2") (pintype "passive"))
      (node (ref "U36") (pin "4") (pinfunction "AVDDL_4") (pintype "power_in"))
      (node (ref "U36") (pin "47") (pinfunction "AVDDL_47") (pintype "power_in"))
      (node (ref "U36") (pin "9") (pinfunction "AVDDL_9") (pintype "power_in"))
    )
    (net (code "46") (name "VDD_1V2_ETH0L") (class "Default")
      (node (ref "C150") (pin "1") (pinfunction "1_1") (pintype "passive"))
      (node (ref "C151") (pin "1") (pinfunction "1_1") (pintype "passive"))
      (node (ref "L5") (pin "2") (pinfunction "2_2") (pintype "passive"))
      (node (ref "R208") (pin "1") (pinfunction "1_1") (pintype "passive"))
      (node (ref "R209") (pin "1") (pinfunction "1_1") (pintype "passive"))
    )
    (net (code "47") (name "VDD_1V2_L0L") (class "Default")
      (node (ref "C157") (pin "1") (pinfunction "1_1") (pintype "passive"))
      (node (ref "C158") (pin "1") (pinfunction "1_1") (pintype "passive"))
      (node (ref "R208") (pin "2") (pinfunction "2_2") (pintype "passive"))
      (node (ref "U36") (pin "22") (pinfunction "DVDDL_22") (pintype "power_in"))
    )
    (net (code "48") (name "VDD_3V3_DRG0") (class "Default")
      (node (ref "C163") (pin "1") (pinfunction "1_1") (pintype "passive"))
      (node (ref "C164") (pin "1") (pinfunction "1_1") (pintype "passive"))
      (node (ref "R196") (pin "2") (pinfunction "2_2") (pintype "passive"))
      (node (ref "R198") (pin "2") (pinfunction "2_2") (pintype "passive"))
      (node (ref "R200") (pin "2") (pinfunction "2_2") (pintype "passive"))
      (node (ref "R201") (pin "2") (pinfunction "2_2") (pintype "passive"))
      (node (ref "R202") (pin "2") (pinfunction "2_2") (pintype "passive"))
      (node (ref "R203") (pin "2") (pinfunction "2_2") (pintype "passive"))
      (node (ref "R205") (pin "2") (pinfunction "2_2") (pintype "passive"))
      (node (ref "U36") (pin "29") (pinfunction "DVDD_RGMII_29") (pintype "power_in"))
    )
    (net (code "49") (name "VDD_3V3_ETH0") (class "Default")
      (node (ref "C152") (pin "1") (pinfunction "1_1") (pintype "passive"))
      (node (ref "C165") (pin "1") (pinfunction "1_1") (pintype "passive"))
      (node (ref "C166") (pin "1") (pinfunction "1_1") (pintype "passive"))
      (node (ref "D11") (pin "1") (pinfunction "Cathode_1") (pintype "passive"))
      (node (ref "R173") (pin "2") (pinfunction "2_2") (pintype "passive"))
      (node (ref "R174") (pin "1") (pinfunction "1_1") (pintype "passive"))
      (node (ref "R179") (pin "1") (pinfunction "1_1") (pintype "passive"))
      (node (ref "R193") (pin "1") (pinfunction "1_1") (pintype "passive"))
      (node (ref "R194") (pin "2") (pinfunction "2_2") (pintype "passive"))
      (node (ref "R195") (pin "2") (pinfunction "2_2") (pintype "passive"))
      (node (ref "R196") (pin "1") (pinfunction "1_1") (pintype "passive"))
      (node (ref "R197") (pin "1") (pinfunction "1_1") (pintype "passive"))
      (node (ref "R199") (pin "2") (pinfunction "2_2") (pintype "passive"))
      (node (ref "R204") (pin "1") (pinfunction "1_1") (pintype "passive"))
      (node (ref "R206") (pin "2") (pinfunction "2_2") (pintype "passive"))
      (node (ref "R207") (pin "2") (pinfunction "2_2") (pintype "passive"))
      (node (ref "U39") (pin "5") (pinfunction "VCC_5") (pintype "passive"))
    )
    (net (code "50") (name "VDD_3V3_ETH0A") (class "Default")
      (node (ref "C159") (pin "1") (pinfunction "1_1") (pintype "passive"))
      (node (ref "C160") (pin "1") (pinfunction "1_1") (pintype "passive"))
      (node (ref "R204") (pin "2") (pinfunction "2_2") (pintype "passive"))
      (node (ref "U36") (pin "1") (pinfunction "AVDD33_1") (pintype "power_in"))
      (node (ref "U36") (pin "12") (pinfunction "AVDD33_12") (pintype "power_in"))
    )
    (net (code "51") (name "VDD_3V3_MAIN") (class "Default")
      (node (ref "R195") (pin "1") (pinfunction "1_1") (pintype "passive"))
    )
    (net (code "52") (name "VDD_3V3_REG0") (class "Default")
      (node (ref "C161") (pin "1") (pinfunction "1_1") (pintype "passive"))
      (node (ref "C162") (pin "1") (pinfunction "1_1") (pintype "passive"))
      (node (ref "R197") (pin "2") (pinfunction "2_2") (pintype "passive"))
      (node (ref "U36") (pin "30") (pinfunction "DVDD33_30") (pintype "power_in"))
      (node (ref "U36") (pin "31") (pinfunction "VDD33_LX_31") (pintype "power_in"))
    )
    (net (code "53") (name "W1{slash}RGMII_RXD1_M0{slash}3V3") (class "Default")
      (node (ref "R187") (pin "1") (pinfunction "1_1") (pintype "passive"))
    )
    (net (code "54") (name "W2{slash}RGMII_RXD2_M0{slash}3V3") (class "Default")
      (node (ref "R188") (pin "1") (pinfunction "1_1") (pintype "passive"))
    )
    (net (code "55") (name "W3{slash}RGMII_RXD0_M0{slash}3V3") (class "Default")
      (node (ref "R185") (pin "1") (pinfunction "1_1") (pintype "passive"))
    )
    (net (code "56") (name "XL9555_P10{slash}RGMII_RST{slash}3V3") (class "Default")
      (node (ref "R193") (pin "2") (pinfunction "2_2") (pintype "passive"))
      (node (ref "U39") (pin "1") (pinfunction "A_1") (pintype "passive"))
    )
    (net (code "57") (name "Y2{slash}RGMII_TXCLK_M0{slash}3V3") (class "Default")
      (node (ref "U36") (pin "21") (pinfunction "TX_CLK_21") (pintype "passive"))
    )
    (net (code "58") (name "Y3{slash}RGMII_RXD3_M0{slash}3V3") (class "Default")
      (node (ref "R189") (pin "1") (pinfunction "1_1") (pintype "passive"))
    )
    (net (code "59") (name "unconnected-(CON12-MH1-Pad15)") (class "Default")
      (node (ref "CON12") (pin "15") (pinfunction "MH1_15") (pintype "passive+no_connect"))
    )
    (net (code "60") (name "unconnected-(CON12-MH2-Pad16)") (class "Default")
      (node (ref "CON12") (pin "16") (pinfunction "MH2_16") (pintype "passive+no_connect"))
    )
    (net (code "61") (name "unconnected-(U36-HSIN-Pad39)") (class "Default")
      (node (ref "U36") (pin "39") (pinfunction "HSIN_39") (pintype "passive+no_connect"))
    )
    (net (code "62") (name "unconnected-(U36-HSIP-Pad38)") (class "Default")
      (node (ref "U36") (pin "38") (pinfunction "HSIP_38") (pintype "passive+no_connect"))
    )
    (net (code "63") (name "unconnected-(U36-HSON-Pad41)") (class "Default")
      (node (ref "U36") (pin "41") (pinfunction "HSON_41") (pintype "passive+no_connect"))
    )
    (net (code "64") (name "unconnected-(U36-HSOP-Pad40)") (class "Default")
      (node (ref "U36") (pin "40") (pinfunction "HSOP_40") (pintype "passive+no_connect"))
    )
    (net (code "65") (name "unconnected-(U36-NC-Pad42)") (class "Default")
      (node (ref "U36") (pin "42") (pinfunction "NC_42") (pintype "passive+no_connect"))
    )
    (net (code "66") (name "unconnected-(U36-Reserved2-Pad43)") (class "Default")
      (node (ref "U36") (pin "43") (pinfunction "Reserved2_43") (pintype "passive+no_connect"))
    )
  )
)
